# Noctua.net
KiCad netlist of a schematic drawn in EAGLE
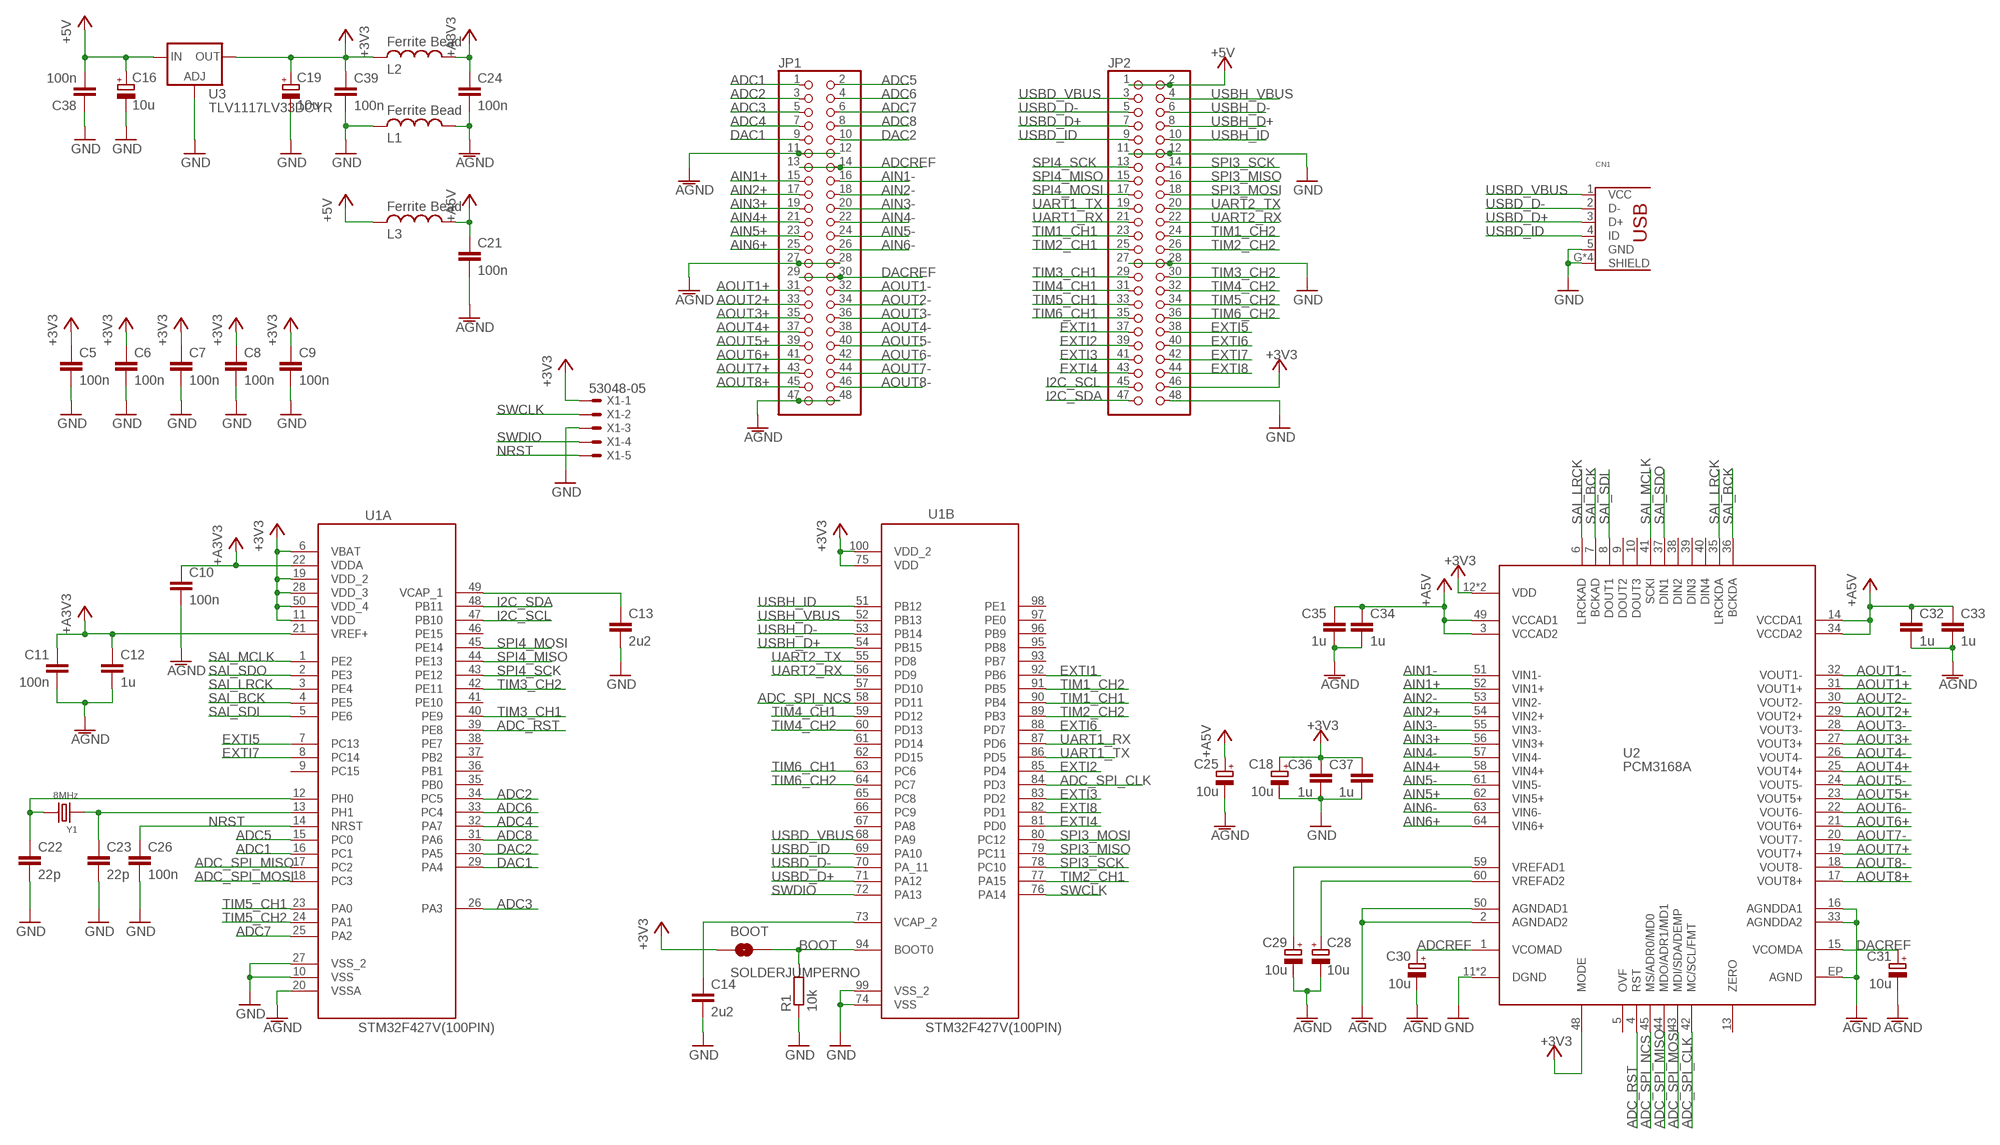
[diagram p0: schematic, sheet 1]

(export (version "E")
  (design (tool "Eeschema 10.0.6"))
  (components
    (comp (ref "BOOT")
      (value "SOLDERJUMPERNO")
      (footprint "eagle-import:SJ_2S-NO")
      (libsource (lib "eagle-import") (part "SOLDERJUMPERNO"))
    )
    (comp (ref "C5")
      (value "100n")
      (footprint "eagle-import:C0603")
      (libsource (lib "eagle-import") (part "C-EUC0603"))
    )
    (comp (ref "C6")
      (value "100n")
      (footprint "eagle-import:C0603")
      (libsource (lib "eagle-import") (part "C-EUC0603"))
    )
    (comp (ref "C7")
      (value "100n")
      (footprint "eagle-import:C0603")
      (libsource (lib "eagle-import") (part "C-EUC0603"))
    )
    (comp (ref "C8")
      (value "100n")
      (footprint "eagle-import:C0603")
      (libsource (lib "eagle-import") (part "C-EUC0603"))
    )
    (comp (ref "C9")
      (value "100n")
      (footprint "eagle-import:C0603")
      (libsource (lib "eagle-import") (part "C-EUC0603"))
    )
    (comp (ref "C10")
      (value "100n")
      (footprint "eagle-import:C0603")
      (libsource (lib "eagle-import") (part "C-EUC0603"))
    )
    (comp (ref "C11")
      (value "100n")
      (footprint "eagle-import:C0603")
      (libsource (lib "eagle-import") (part "C-EUC0603"))
    )
    (comp (ref "C12")
      (value "1u")
      (footprint "eagle-import:C0603")
      (libsource (lib "eagle-import") (part "C-EUC0603"))
    )
    (comp (ref "C13")
      (value "2u2")
      (footprint "eagle-import:C0603")
      (libsource (lib "eagle-import") (part "C-EUC0603"))
    )
    (comp (ref "C14")
      (value "2u2")
      (footprint "eagle-import:C0603")
      (libsource (lib "eagle-import") (part "C-EUC0603"))
    )
    (comp (ref "C16")
      (value "10u")
      (footprint "eagle-import:UD-4X5,8_NICHICON")
      (libsource (lib "eagle-import") (part "CPOL-EUUD-4X5,8"))
    )
    (comp (ref "C18")
      (value "10u")
      (footprint "eagle-import:UD-4X5,8_NICHICON")
      (libsource (lib "eagle-import") (part "CPOL-EUUD-4X5,8"))
    )
    (comp (ref "C19")
      (value "10u")
      (footprint "eagle-import:UD-4X5,8_NICHICON")
      (libsource (lib "eagle-import") (part "CPOL-EUUD-4X5,8"))
    )
    (comp (ref "C21")
      (value "100n")
      (footprint "eagle-import:C0603")
      (libsource (lib "eagle-import") (part "C-EUC0603"))
    )
    (comp (ref "C22")
      (value "22p")
      (footprint "eagle-import:C0603")
      (libsource (lib "eagle-import") (part "C-EUC0603"))
    )
    (comp (ref "C23")
      (value "22p")
      (footprint "eagle-import:C0603")
      (libsource (lib "eagle-import") (part "C-EUC0603"))
    )
    (comp (ref "C24")
      (value "100n")
      (footprint "eagle-import:C0603")
      (libsource (lib "eagle-import") (part "C-EUC0603"))
    )
    (comp (ref "C25")
      (value "10u")
      (footprint "eagle-import:UD-4X5,8_NICHICON")
      (libsource (lib "eagle-import") (part "CPOL-EUUD-4X5,8"))
    )
    (comp (ref "C26")
      (value "100n")
      (footprint "eagle-import:C0603")
      (libsource (lib "eagle-import") (part "C-EUC0603"))
    )
    (comp (ref "C28")
      (value "10u")
      (footprint "eagle-import:UD-4X5,8_NICHICON")
      (libsource (lib "eagle-import") (part "CPOL-EUUD-4X5,8"))
    )
    (comp (ref "C29")
      (value "10u")
      (footprint "eagle-import:UD-4X5,8_NICHICON")
      (libsource (lib "eagle-import") (part "CPOL-EUUD-4X5,8"))
    )
    (comp (ref "C30")
      (value "10u")
      (footprint "eagle-import:UD-4X5,8_NICHICON")
      (libsource (lib "eagle-import") (part "CPOL-EUUD-4X5,8"))
    )
    (comp (ref "C31")
      (value "10u")
      (footprint "eagle-import:UD-4X5,8_NICHICON")
      (libsource (lib "eagle-import") (part "CPOL-EUUD-4X5,8"))
    )
    (comp (ref "C32")
      (value "1u")
      (footprint "eagle-import:C0603")
      (libsource (lib "eagle-import") (part "C-EUC0603"))
    )
    (comp (ref "C33")
      (value "1u")
      (footprint "eagle-import:C0603")
      (libsource (lib "eagle-import") (part "C-EUC0603"))
    )
    (comp (ref "C34")
      (value "1u")
      (footprint "eagle-import:C0603")
      (libsource (lib "eagle-import") (part "C-EUC0603"))
    )
    (comp (ref "C35")
      (value "1u")
      (footprint "eagle-import:C0603")
      (libsource (lib "eagle-import") (part "C-EUC0603"))
    )
    (comp (ref "C36")
      (value "1u")
      (footprint "eagle-import:C0603")
      (libsource (lib "eagle-import") (part "C-EUC0603"))
    )
    (comp (ref "C37")
      (value "1u")
      (footprint "eagle-import:C0603")
      (libsource (lib "eagle-import") (part "C-EUC0603"))
    )
    (comp (ref "C38")
      (value "100n")
      (footprint "eagle-import:C0603")
      (libsource (lib "eagle-import") (part "C-EUC0603"))
    )
    (comp (ref "C39")
      (value "100n")
      (footprint "eagle-import:C0603")
      (libsource (lib "eagle-import") (part "C-EUC0603"))
    )
    (comp (ref "CN1")
      (value "USB_HRS_ZX62-B-5PA(11)MICRO.B")
      (footprint "eagle-import:HRS_ZX62RD-AB-5P8")
      (libsource (lib "eagle-import") (part "USB_HRS_ZX62-B-5PA(11)MICRO.B"))
    )
    (comp (ref "JP1")
      (value "PINHD-2X24")
      (footprint "eagle-import:2X24")
      (libsource (lib "eagle-import") (part "PINHD-2X24"))
    )
    (comp (ref "JP2")
      (value "PINHD-2X24")
      (footprint "eagle-import:2X24")
      (libsource (lib "eagle-import") (part "PINHD-2X24"))
    )
    (comp (ref "L1")
      (value "Ferrite Bead")
      (footprint "eagle-import:0603")
      (libsource (lib "eagle-import") (part "INDUCTOR"))
    )
    (comp (ref "L2")
      (value "Ferrite Bead")
      (footprint "eagle-import:0603")
      (libsource (lib "eagle-import") (part "INDUCTOR"))
    )
    (comp (ref "L3")
      (value "Ferrite Bead")
      (footprint "eagle-import:0603")
      (libsource (lib "eagle-import") (part "INDUCTOR"))
    )
    (comp (ref "R1")
      (value "10k")
      (footprint "eagle-import:0603@1")
      (libsource (lib "eagle-import") (part "R-EU_0603"))
    )
    (comp (ref "U1")
      (value "STM32F427V(100PIN)")
      (footprint "eagle-import:QFP50P1600X1600X160-100N")
      (libsource (lib "eagle-import") (part "STM32F42XV/43XV(100PIN)"))
    )
    (comp (ref "U2")
      (value "PCM3168A")
      (footprint "eagle-import:PQFP64")
      (libsource (lib "eagle-import") (part "PCM3168A"))
    )
    (comp (ref "U3")
      (value "TLV1117LV33DCYR")
      (footprint "eagle-import:SOT223")
      (libsource (lib "eagle-import") (part "LD117A?S33TR"))
    )
    (comp (ref "X1")
      (value "53048-05")
      (footprint "eagle-import:53048-05")
      (fields (field (name "MF") "MOLEX") (field (name "MPN") "53048-0510"))
      (libsource (lib "eagle-import") (part "53?-05048"))
    )
    (comp (ref "Y1")
      (value "8MHz")
      (footprint "eagle-import:X2-SMD-5.0X3.2X1.3MM")
      (fields (field (name "MPN") "5032/2P"))
      (libsource (lib "eagle-import") (part "SMD-CRYSTAL-8MHZ-20PF-20PPM(2P-5.0X3.2MM)"))
    )
  )
  (nets
    (net (code "1") (name "+3V3") (class "Default")
      (node (ref "BOOT") (pin "1") (pinfunction "1_1") (pintype "passive"))
      (node (ref "C18") (pin "+") (pinfunction "+_+") (pintype "passive"))
      (node (ref "C19") (pin "+") (pinfunction "+_+") (pintype "passive"))
      (node (ref "C36") (pin "1") (pinfunction "1_1") (pintype "passive"))
      (node (ref "C37") (pin "1") (pinfunction "1_1") (pintype "passive"))
      (node (ref "C39") (pin "1") (pinfunction "1_1") (pintype "passive"))
      (node (ref "C5") (pin "1") (pinfunction "1_1") (pintype "passive"))
      (node (ref "C6") (pin "1") (pinfunction "1_1") (pintype "passive"))
      (node (ref "C7") (pin "1") (pinfunction "1_1") (pintype "passive"))
      (node (ref "C8") (pin "1") (pinfunction "1_1") (pintype "passive"))
      (node (ref "C9") (pin "1") (pinfunction "1_1") (pintype "passive"))
      (node (ref "JP2") (pin "46") (pinfunction "46_46") (pintype "passive"))
      (node (ref "L2") (pin "2") (pinfunction "2_2") (pintype "passive"))
      (node (ref "U1") (pin "100") (pinfunction "VDD_2_100") (pintype "bidirectional"))
      (node (ref "U1") (pin "11") (pinfunction "VDD_11") (pintype "bidirectional"))
      (node (ref "U1") (pin "19") (pinfunction "VDD_2_19") (pintype "bidirectional"))
      (node (ref "U1") (pin "28") (pinfunction "VDD_3_28") (pintype "bidirectional"))
      (node (ref "U1") (pin "50") (pinfunction "VDD_4_50") (pintype "bidirectional"))
      (node (ref "U1") (pin "6") (pinfunction "VBAT_6") (pintype "bidirectional"))
      (node (ref "U1") (pin "75") (pinfunction "VDD_75") (pintype "bidirectional"))
      (node (ref "U2") (pin "12") (pinfunction "VDD_12") (pintype "bidirectional"))
      (node (ref "U2") (pin "46") (pinfunction "VDD_46") (pintype "bidirectional"))
      (node (ref "U2") (pin "48") (pinfunction "MODE_48") (pintype "bidirectional"))
      (node (ref "U3") (pin "4") (pinfunction "OUT_4") (pintype "passive"))
      (node (ref "X1") (pin "1") (pinfunction "S_1") (pintype "passive"))
    )
    (net (code "2") (name "+5V") (class "Default")
      (node (ref "C16") (pin "+") (pinfunction "+_+") (pintype "passive"))
      (node (ref "C38") (pin "2") (pinfunction "2_2") (pintype "passive"))
      (node (ref "JP2") (pin "1") (pinfunction "1_1") (pintype "passive"))
      (node (ref "JP2") (pin "2") (pinfunction "2_2") (pintype "passive"))
      (node (ref "L3") (pin "2") (pinfunction "2_2") (pintype "passive"))
      (node (ref "U3") (pin "3") (pinfunction "IN_3") (pintype "input"))
    )
    (net (code "3") (name "+A3V3") (class "Default")
      (node (ref "C10") (pin "1") (pinfunction "1_1") (pintype "passive"))
      (node (ref "C11") (pin "1") (pinfunction "1_1") (pintype "passive"))
      (node (ref "C12") (pin "1") (pinfunction "1_1") (pintype "passive"))
      (node (ref "C24") (pin "1") (pinfunction "1_1") (pintype "passive"))
      (node (ref "L2") (pin "1") (pinfunction "1_1") (pintype "passive"))
      (node (ref "U1") (pin "21") (pinfunction "VREF+_21") (pintype "bidirectional"))
      (node (ref "U1") (pin "22") (pinfunction "VDDA_22") (pintype "bidirectional"))
    )
    (net (code "4") (name "+A5V") (class "Default")
      (node (ref "C21") (pin "1") (pinfunction "1_1") (pintype "passive"))
      (node (ref "C25") (pin "+") (pinfunction "+_+") (pintype "passive"))
      (node (ref "C32") (pin "1") (pinfunction "1_1") (pintype "passive"))
      (node (ref "C33") (pin "1") (pinfunction "1_1") (pintype "passive"))
      (node (ref "C34") (pin "1") (pinfunction "1_1") (pintype "passive"))
      (node (ref "C35") (pin "1") (pinfunction "1_1") (pintype "passive"))
      (node (ref "L3") (pin "1") (pinfunction "1_1") (pintype "passive"))
      (node (ref "U2") (pin "14") (pinfunction "VCCDA1_14") (pintype "bidirectional"))
      (node (ref "U2") (pin "3") (pinfunction "VCCAD2_3") (pintype "bidirectional"))
      (node (ref "U2") (pin "34") (pinfunction "VCCDA2_34") (pintype "bidirectional"))
      (node (ref "U2") (pin "49") (pinfunction "VCCAD1_49") (pintype "bidirectional"))
    )
    (net (code "5") (name "/ADC1") (class "Default")
      (node (ref "JP1") (pin "1") (pinfunction "1_1") (pintype "passive"))
      (node (ref "U1") (pin "16") (pinfunction "PC1_16") (pintype "bidirectional"))
    )
    (net (code "6") (name "/ADC2") (class "Default")
      (node (ref "JP1") (pin "3") (pinfunction "3_3") (pintype "passive"))
      (node (ref "U1") (pin "34") (pinfunction "PC5_34") (pintype "bidirectional"))
    )
    (net (code "7") (name "/ADC3") (class "Default")
      (node (ref "JP1") (pin "5") (pinfunction "5_5") (pintype "passive"))
      (node (ref "U1") (pin "26") (pinfunction "PA3_26") (pintype "bidirectional"))
    )
    (net (code "8") (name "/ADC4") (class "Default")
      (node (ref "JP1") (pin "7") (pinfunction "7_7") (pintype "passive"))
      (node (ref "U1") (pin "32") (pinfunction "PA7_32") (pintype "bidirectional"))
    )
    (net (code "9") (name "/ADC5") (class "Default")
      (node (ref "JP1") (pin "2") (pinfunction "2_2") (pintype "passive"))
      (node (ref "U1") (pin "15") (pinfunction "PC0_15") (pintype "bidirectional"))
    )
    (net (code "10") (name "/ADC6") (class "Default")
      (node (ref "JP1") (pin "4") (pinfunction "4_4") (pintype "passive"))
      (node (ref "U1") (pin "33") (pinfunction "PC4_33") (pintype "bidirectional"))
    )
    (net (code "11") (name "/ADC7") (class "Default")
      (node (ref "JP1") (pin "6") (pinfunction "6_6") (pintype "passive"))
      (node (ref "U1") (pin "25") (pinfunction "PA2_25") (pintype "bidirectional"))
    )
    (net (code "12") (name "/ADC8") (class "Default")
      (node (ref "JP1") (pin "8") (pinfunction "8_8") (pintype "passive"))
      (node (ref "U1") (pin "31") (pinfunction "PA6_31") (pintype "bidirectional"))
    )
    (net (code "13") (name "/ADCREF") (class "Default")
      (node (ref "C30") (pin "+") (pinfunction "+_+") (pintype "passive"))
      (node (ref "JP1") (pin "13") (pinfunction "13_13") (pintype "passive"))
      (node (ref "JP1") (pin "14") (pinfunction "14_14") (pintype "passive"))
      (node (ref "U2") (pin "1") (pinfunction "VCOMAD_1") (pintype "bidirectional"))
    )
    (net (code "14") (name "/ADC_RST") (class "Default")
      (node (ref "U1") (pin "39") (pinfunction "PE8_39") (pintype "bidirectional"))
      (node (ref "U2") (pin "4") (pinfunction "RST_4") (pintype "bidirectional"))
    )
    (net (code "15") (name "/ADC_SPI_CLK") (class "Default")
      (node (ref "U1") (pin "84") (pinfunction "PD3_84") (pintype "bidirectional"))
      (node (ref "U2") (pin "42") (pinfunction "MC/SCL/FMT_42") (pintype "bidirectional"))
    )
    (net (code "16") (name "/ADC_SPI_MISO") (class "Default")
      (node (ref "U1") (pin "17") (pinfunction "PC2_17") (pintype "bidirectional"))
      (node (ref "U2") (pin "44") (pinfunction "MDO/ADR1/MD1_44") (pintype "bidirectional"))
    )
    (net (code "17") (name "/ADC_SPI_MOSI") (class "Default")
      (node (ref "U1") (pin "18") (pinfunction "PC3_18") (pintype "bidirectional"))
      (node (ref "U2") (pin "43") (pinfunction "MDI/SDA/DEMP_43") (pintype "bidirectional"))
    )
    (net (code "18") (name "/ADC_SPI_NCS") (class "Default")
      (node (ref "U1") (pin "58") (pinfunction "PD11_58") (pintype "bidirectional"))
      (node (ref "U2") (pin "45") (pinfunction "MS/ADR0/MD0_45") (pintype "bidirectional"))
    )
    (net (code "19") (name "/AIN1+") (class "Default")
      (node (ref "JP1") (pin "15") (pinfunction "15_15") (pintype "passive"))
      (node (ref "U2") (pin "52") (pinfunction "VIN1+_52") (pintype "bidirectional"))
    )
    (net (code "20") (name "/AIN1-") (class "Default")
      (node (ref "JP1") (pin "16") (pinfunction "16_16") (pintype "passive"))
      (node (ref "U2") (pin "51") (pinfunction "VIN1-_51") (pintype "bidirectional"))
    )
    (net (code "21") (name "/AIN2+") (class "Default")
      (node (ref "JP1") (pin "17") (pinfunction "17_17") (pintype "passive"))
      (node (ref "U2") (pin "54") (pinfunction "VIN2+_54") (pintype "bidirectional"))
    )
    (net (code "22") (name "/AIN2-") (class "Default")
      (node (ref "JP1") (pin "18") (pinfunction "18_18") (pintype "passive"))
      (node (ref "U2") (pin "53") (pinfunction "VIN2-_53") (pintype "bidirectional"))
    )
    (net (code "23") (name "/AIN3+") (class "Default")
      (node (ref "JP1") (pin "19") (pinfunction "19_19") (pintype "passive"))
      (node (ref "U2") (pin "56") (pinfunction "VIN3+_56") (pintype "bidirectional"))
    )
    (net (code "24") (name "/AIN3-") (class "Default")
      (node (ref "JP1") (pin "20") (pinfunction "20_20") (pintype "passive"))
      (node (ref "U2") (pin "55") (pinfunction "VIN3-_55") (pintype "bidirectional"))
    )
    (net (code "25") (name "/AIN4+") (class "Default")
      (node (ref "JP1") (pin "21") (pinfunction "21_21") (pintype "passive"))
      (node (ref "U2") (pin "58") (pinfunction "VIN4+_58") (pintype "bidirectional"))
    )
    (net (code "26") (name "/AIN4-") (class "Default")
      (node (ref "JP1") (pin "22") (pinfunction "22_22") (pintype "passive"))
      (node (ref "U2") (pin "57") (pinfunction "VIN4-_57") (pintype "bidirectional"))
    )
    (net (code "27") (name "/AIN5+") (class "Default")
      (node (ref "JP1") (pin "23") (pinfunction "23_23") (pintype "passive"))
      (node (ref "U2") (pin "62") (pinfunction "VIN5+_62") (pintype "bidirectional"))
    )
    (net (code "28") (name "/AIN5-") (class "Default")
      (node (ref "JP1") (pin "24") (pinfunction "24_24") (pintype "passive"))
      (node (ref "U2") (pin "61") (pinfunction "VIN5-_61") (pintype "bidirectional"))
    )
    (net (code "29") (name "/AIN6+") (class "Default")
      (node (ref "JP1") (pin "25") (pinfunction "25_25") (pintype "passive"))
      (node (ref "U2") (pin "64") (pinfunction "VIN6+_64") (pintype "bidirectional"))
    )
    (net (code "30") (name "/AIN6-") (class "Default")
      (node (ref "JP1") (pin "26") (pinfunction "26_26") (pintype "passive"))
      (node (ref "U2") (pin "63") (pinfunction "VIN6-_63") (pintype "bidirectional"))
    )
    (net (code "31") (name "/AOUT1+") (class "Default")
      (node (ref "JP1") (pin "31") (pinfunction "31_31") (pintype "passive"))
      (node (ref "U2") (pin "31") (pinfunction "VOUT1+_31") (pintype "bidirectional"))
    )
    (net (code "32") (name "/AOUT1-") (class "Default")
      (node (ref "JP1") (pin "32") (pinfunction "32_32") (pintype "passive"))
      (node (ref "U2") (pin "32") (pinfunction "VOUT1-_32") (pintype "bidirectional"))
    )
    (net (code "33") (name "/AOUT2+") (class "Default")
      (node (ref "JP1") (pin "33") (pinfunction "33_33") (pintype "passive"))
      (node (ref "U2") (pin "29") (pinfunction "VOUT2+_29") (pintype "bidirectional"))
    )
    (net (code "34") (name "/AOUT2-") (class "Default")
      (node (ref "JP1") (pin "34") (pinfunction "34_34") (pintype "passive"))
      (node (ref "U2") (pin "30") (pinfunction "VOUT2-_30") (pintype "bidirectional"))
    )
    (net (code "35") (name "/AOUT3+") (class "Default")
      (node (ref "JP1") (pin "35") (pinfunction "35_35") (pintype "passive"))
      (node (ref "U2") (pin "27") (pinfunction "VOUT3+_27") (pintype "bidirectional"))
    )
    (net (code "36") (name "/AOUT3-") (class "Default")
      (node (ref "JP1") (pin "36") (pinfunction "36_36") (pintype "passive"))
      (node (ref "U2") (pin "28") (pinfunction "VOUT3-_28") (pintype "bidirectional"))
    )
    (net (code "37") (name "/AOUT4+") (class "Default")
      (node (ref "JP1") (pin "37") (pinfunction "37_37") (pintype "passive"))
      (node (ref "U2") (pin "25") (pinfunction "VOUT4+_25") (pintype "bidirectional"))
    )
    (net (code "38") (name "/AOUT4-") (class "Default")
      (node (ref "JP1") (pin "38") (pinfunction "38_38") (pintype "passive"))
      (node (ref "U2") (pin "26") (pinfunction "VOUT4-_26") (pintype "bidirectional"))
    )
    (net (code "39") (name "/AOUT5+") (class "Default")
      (node (ref "JP1") (pin "39") (pinfunction "39_39") (pintype "passive"))
      (node (ref "U2") (pin "23") (pinfunction "VOUT5+_23") (pintype "bidirectional"))
    )
    (net (code "40") (name "/AOUT5-") (class "Default")
      (node (ref "JP1") (pin "40") (pinfunction "40_40") (pintype "passive"))
      (node (ref "U2") (pin "24") (pinfunction "VOUT5-_24") (pintype "bidirectional"))
    )
    (net (code "41") (name "/AOUT6+") (class "Default")
      (node (ref "JP1") (pin "41") (pinfunction "41_41") (pintype "passive"))
      (node (ref "U2") (pin "21") (pinfunction "VOUT6+_21") (pintype "bidirectional"))
    )
    (net (code "42") (name "/AOUT6-") (class "Default")
      (node (ref "JP1") (pin "42") (pinfunction "42_42") (pintype "passive"))
      (node (ref "U2") (pin "22") (pinfunction "VOUT6-_22") (pintype "bidirectional"))
    )
    (net (code "43") (name "/AOUT7+") (class "Default")
      (node (ref "JP1") (pin "43") (pinfunction "43_43") (pintype "passive"))
      (node (ref "U2") (pin "19") (pinfunction "VOUT7+_19") (pintype "bidirectional"))
    )
    (net (code "44") (name "/AOUT7-") (class "Default")
      (node (ref "JP1") (pin "44") (pinfunction "44_44") (pintype "passive"))
      (node (ref "U2") (pin "20") (pinfunction "VOUT7-_20") (pintype "bidirectional"))
    )
    (net (code "45") (name "/AOUT8+") (class "Default")
      (node (ref "JP1") (pin "45") (pinfunction "45_45") (pintype "passive"))
      (node (ref "U2") (pin "17") (pinfunction "VOUT8+_17") (pintype "bidirectional"))
    )
    (net (code "46") (name "/AOUT8-") (class "Default")
      (node (ref "JP1") (pin "46") (pinfunction "46_46") (pintype "passive"))
      (node (ref "U2") (pin "18") (pinfunction "VOUT8-_18") (pintype "bidirectional"))
    )
    (net (code "47") (name "/BOOT") (class "Default")
      (node (ref "BOOT") (pin "2") (pinfunction "2_2") (pintype "passive"))
      (node (ref "R1") (pin "2") (pinfunction "2_2") (pintype "passive"))
      (node (ref "U1") (pin "94") (pinfunction "BOOT0_94") (pintype "bidirectional"))
    )
    (net (code "48") (name "/DAC1") (class "Default")
      (node (ref "JP1") (pin "9") (pinfunction "9_9") (pintype "passive"))
      (node (ref "U1") (pin "29") (pinfunction "PA4_29") (pintype "bidirectional"))
    )
    (net (code "49") (name "/DAC2") (class "Default")
      (node (ref "JP1") (pin "10") (pinfunction "10_10") (pintype "passive"))
      (node (ref "U1") (pin "30") (pinfunction "PA5_30") (pintype "bidirectional"))
    )
    (net (code "50") (name "/DACREF") (class "Default")
      (node (ref "C31") (pin "+") (pinfunction "+_+") (pintype "passive"))
      (node (ref "JP1") (pin "29") (pinfunction "29_29") (pintype "passive"))
      (node (ref "JP1") (pin "30") (pinfunction "30_30") (pintype "passive"))
      (node (ref "U2") (pin "15") (pinfunction "VCOMDA_15") (pintype "bidirectional"))
    )
    (net (code "51") (name "/EXTI1") (class "Default")
      (node (ref "JP2") (pin "37") (pinfunction "37_37") (pintype "passive"))
      (node (ref "U1") (pin "92") (pinfunction "PB6_92") (pintype "bidirectional"))
    )
    (net (code "52") (name "/EXTI2") (class "Default")
      (node (ref "JP2") (pin "39") (pinfunction "39_39") (pintype "passive"))
      (node (ref "U1") (pin "85") (pinfunction "PD4_85") (pintype "bidirectional"))
    )
    (net (code "53") (name "/EXTI3") (class "Default")
      (node (ref "JP2") (pin "41") (pinfunction "41_41") (pintype "passive"))
      (node (ref "U1") (pin "83") (pinfunction "PD2_83") (pintype "bidirectional"))
    )
    (net (code "54") (name "/EXTI4") (class "Default")
      (node (ref "JP2") (pin "43") (pinfunction "43_43") (pintype "passive"))
      (node (ref "U1") (pin "81") (pinfunction "PD0_81") (pintype "bidirectional"))
    )
    (net (code "55") (name "/EXTI5") (class "Default")
      (node (ref "JP2") (pin "38") (pinfunction "38_38") (pintype "passive"))
      (node (ref "U1") (pin "7") (pinfunction "PC13_7") (pintype "bidirectional"))
    )
    (net (code "56") (name "/EXTI6") (class "Default")
      (node (ref "JP2") (pin "40") (pinfunction "40_40") (pintype "passive"))
      (node (ref "U1") (pin "88") (pinfunction "PD7_88") (pintype "bidirectional"))
    )
    (net (code "57") (name "/EXTI7") (class "Default")
      (node (ref "JP2") (pin "42") (pinfunction "42_42") (pintype "passive"))
      (node (ref "U1") (pin "8") (pinfunction "PC14_8") (pintype "bidirectional"))
    )
    (net (code "58") (name "/EXTI8") (class "Default")
      (node (ref "JP2") (pin "44") (pinfunction "44_44") (pintype "passive"))
      (node (ref "U1") (pin "82") (pinfunction "PD1_82") (pintype "bidirectional"))
    )
    (net (code "59") (name "/I2C_SCL") (class "Default")
      (node (ref "JP2") (pin "45") (pinfunction "45_45") (pintype "passive"))
      (node (ref "U1") (pin "47") (pinfunction "PB10_47") (pintype "bidirectional"))
    )
    (net (code "60") (name "/I2C_SDA") (class "Default")
      (node (ref "JP2") (pin "47") (pinfunction "47_47") (pintype "passive"))
      (node (ref "U1") (pin "48") (pinfunction "PB11_48") (pintype "bidirectional"))
    )
    (net (code "61") (name "/NRST") (class "Default")
      (node (ref "C26") (pin "1") (pinfunction "1_1") (pintype "passive"))
      (node (ref "U1") (pin "14") (pinfunction "NRST_14") (pintype "bidirectional"))
      (node (ref "X1") (pin "5") (pinfunction "S_5") (pintype "passive"))
    )
    (net (code "62") (name "/SAI_BCK") (class "Default")
      (node (ref "U1") (pin "4") (pinfunction "PE5_4") (pintype "bidirectional"))
      (node (ref "U2") (pin "36") (pinfunction "BCKDA_36") (pintype "bidirectional"))
      (node (ref "U2") (pin "7") (pinfunction "BCKAD_7") (pintype "bidirectional"))
    )
    (net (code "63") (name "/SAI_LRCK") (class "Default")
      (node (ref "U1") (pin "3") (pinfunction "PE4_3") (pintype "bidirectional"))
      (node (ref "U2") (pin "35") (pinfunction "LRCKDA_35") (pintype "bidirectional"))
      (node (ref "U2") (pin "6") (pinfunction "LRCKAD_6") (pintype "bidirectional"))
    )
    (net (code "64") (name "/SAI_MCLK") (class "Default")
      (node (ref "U1") (pin "1") (pinfunction "PE2_1") (pintype "bidirectional"))
      (node (ref "U2") (pin "41") (pinfunction "SCKI_41") (pintype "bidirectional"))
    )
    (net (code "65") (name "/SAI_SDI") (class "Default")
      (node (ref "U1") (pin "5") (pinfunction "PE6_5") (pintype "bidirectional"))
      (node (ref "U2") (pin "8") (pinfunction "DOUT1_8") (pintype "bidirectional"))
    )
    (net (code "66") (name "/SAI_SDO") (class "Default")
      (node (ref "U1") (pin "2") (pinfunction "PE3_2") (pintype "bidirectional"))
      (node (ref "U2") (pin "37") (pinfunction "DIN1_37") (pintype "bidirectional"))
    )
    (net (code "67") (name "/SPI3_MISO") (class "Default")
      (node (ref "JP2") (pin "16") (pinfunction "16_16") (pintype "passive"))
      (node (ref "U1") (pin "79") (pinfunction "PC11_79") (pintype "bidirectional"))
    )
    (net (code "68") (name "/SPI3_MOSI") (class "Default")
      (node (ref "JP2") (pin "18") (pinfunction "18_18") (pintype "passive"))
      (node (ref "U1") (pin "80") (pinfunction "PC12_80") (pintype "bidirectional"))
    )
    (net (code "69") (name "/SPI3_SCK") (class "Default")
      (node (ref "JP2") (pin "14") (pinfunction "14_14") (pintype "passive"))
      (node (ref "U1") (pin "78") (pinfunction "PC10_78") (pintype "bidirectional"))
    )
    (net (code "70") (name "/SPI4_MISO") (class "Default")
      (node (ref "JP2") (pin "15") (pinfunction "15_15") (pintype "passive"))
      (node (ref "U1") (pin "44") (pinfunction "PE13_44") (pintype "bidirectional"))
    )
    (net (code "71") (name "/SPI4_MOSI") (class "Default")
      (node (ref "JP2") (pin "17") (pinfunction "17_17") (pintype "passive"))
      (node (ref "U1") (pin "45") (pinfunction "PE14_45") (pintype "bidirectional"))
    )
    (net (code "72") (name "/SPI4_SCK") (class "Default")
      (node (ref "JP2") (pin "13") (pinfunction "13_13") (pintype "passive"))
      (node (ref "U1") (pin "43") (pinfunction "PE12_43") (pintype "bidirectional"))
    )
    (net (code "73") (name "/SWCLK") (class "Default")
      (node (ref "U1") (pin "76") (pinfunction "PA14_76") (pintype "bidirectional"))
      (node (ref "X1") (pin "2") (pinfunction "S_2") (pintype "passive"))
    )
    (net (code "74") (name "/SWDIO") (class "Default")
      (node (ref "U1") (pin "72") (pinfunction "PA13_72") (pintype "bidirectional"))
      (node (ref "X1") (pin "4") (pinfunction "S_4") (pintype "passive"))
    )
    (net (code "75") (name "/TIM1_CH1") (class "Default")
      (node (ref "JP2") (pin "23") (pinfunction "23_23") (pintype "passive"))
      (node (ref "U1") (pin "90") (pinfunction "PB4_90") (pintype "bidirectional"))
    )
    (net (code "76") (name "/TIM1_CH2") (class "Default")
      (node (ref "JP2") (pin "24") (pinfunction "24_24") (pintype "passive"))
      (node (ref "U1") (pin "91") (pinfunction "PB5_91") (pintype "bidirectional"))
    )
    (net (code "77") (name "/TIM2_CH1") (class "Default")
      (node (ref "JP2") (pin "25") (pinfunction "25_25") (pintype "passive"))
      (node (ref "U1") (pin "77") (pinfunction "PA15_77") (pintype "bidirectional"))
    )
    (net (code "78") (name "/TIM2_CH2") (class "Default")
      (node (ref "JP2") (pin "26") (pinfunction "26_26") (pintype "passive"))
      (node (ref "U1") (pin "89") (pinfunction "PB3_89") (pintype "bidirectional"))
    )
    (net (code "79") (name "/TIM3_CH1") (class "Default")
      (node (ref "JP2") (pin "29") (pinfunction "29_29") (pintype "passive"))
      (node (ref "U1") (pin "40") (pinfunction "PE9_40") (pintype "bidirectional"))
    )
    (net (code "80") (name "/TIM3_CH2") (class "Default")
      (node (ref "JP2") (pin "30") (pinfunction "30_30") (pintype "passive"))
      (node (ref "U1") (pin "42") (pinfunction "PE11_42") (pintype "bidirectional"))
    )
    (net (code "81") (name "/TIM4_CH1") (class "Default")
      (node (ref "JP2") (pin "31") (pinfunction "31_31") (pintype "passive"))
      (node (ref "U1") (pin "59") (pinfunction "PD12_59") (pintype "bidirectional"))
    )
    (net (code "82") (name "/TIM4_CH2") (class "Default")
      (node (ref "JP2") (pin "32") (pinfunction "32_32") (pintype "passive"))
      (node (ref "U1") (pin "60") (pinfunction "PD13_60") (pintype "bidirectional"))
    )
    (net (code "83") (name "/TIM5_CH1") (class "Default")
      (node (ref "JP2") (pin "33") (pinfunction "33_33") (pintype "passive"))
      (node (ref "U1") (pin "23") (pinfunction "PA0_23") (pintype "bidirectional"))
    )
    (net (code "84") (name "/TIM5_CH2") (class "Default")
      (node (ref "JP2") (pin "34") (pinfunction "34_34") (pintype "passive"))
      (node (ref "U1") (pin "24") (pinfunction "PA1_24") (pintype "bidirectional"))
    )
    (net (code "85") (name "/TIM6_CH1") (class "Default")
      (node (ref "JP2") (pin "35") (pinfunction "35_35") (pintype "passive"))
      (node (ref "U1") (pin "63") (pinfunction "PC6_63") (pintype "bidirectional"))
    )
    (net (code "86") (name "/TIM6_CH2") (class "Default")
      (node (ref "JP2") (pin "36") (pinfunction "36_36") (pintype "passive"))
      (node (ref "U1") (pin "64") (pinfunction "PC7_64") (pintype "bidirectional"))
    )
    (net (code "87") (name "/UART1_RX") (class "Default")
      (node (ref "JP2") (pin "21") (pinfunction "21_21") (pintype "passive"))
      (node (ref "U1") (pin "87") (pinfunction "PD6_87") (pintype "bidirectional"))
    )
    (net (code "88") (name "/UART1_TX") (class "Default")
      (node (ref "JP2") (pin "19") (pinfunction "19_19") (pintype "passive"))
      (node (ref "U1") (pin "86") (pinfunction "PD5_86") (pintype "bidirectional"))
    )
    (net (code "89") (name "/UART2_RX") (class "Default")
      (node (ref "JP2") (pin "22") (pinfunction "22_22") (pintype "passive"))
      (node (ref "U1") (pin "56") (pinfunction "PD9_56") (pintype "bidirectional"))
    )
    (net (code "90") (name "/UART2_TX") (class "Default")
      (node (ref "JP2") (pin "20") (pinfunction "20_20") (pintype "passive"))
      (node (ref "U1") (pin "55") (pinfunction "PD8_55") (pintype "bidirectional"))
    )
    (net (code "91") (name "/USBD_D+") (class "Default")
      (node (ref "CN1") (pin "3") (pinfunction "D+_3") (pintype "bidirectional"))
      (node (ref "JP2") (pin "7") (pinfunction "7_7") (pintype "passive"))
      (node (ref "U1") (pin "71") (pinfunction "PA12_71") (pintype "bidirectional"))
    )
    (net (code "92") (name "/USBD_D-") (class "Default")
      (node (ref "CN1") (pin "2") (pinfunction "D-_2") (pintype "bidirectional"))
      (node (ref "JP2") (pin "5") (pinfunction "5_5") (pintype "passive"))
      (node (ref "U1") (pin "70") (pinfunction "PA_11_70") (pintype "bidirectional"))
    )
    (net (code "93") (name "/USBD_ID") (class "Default")
      (node (ref "CN1") (pin "4") (pinfunction "ID_4") (pintype "bidirectional"))
      (node (ref "JP2") (pin "9") (pinfunction "9_9") (pintype "passive"))
      (node (ref "U1") (pin "69") (pinfunction "PA10_69") (pintype "bidirectional"))
    )
    (net (code "94") (name "/USBD_VBUS") (class "Default")
      (node (ref "CN1") (pin "1") (pinfunction "VCC_1") (pintype "bidirectional"))
      (node (ref "JP2") (pin "3") (pinfunction "3_3") (pintype "passive"))
      (node (ref "U1") (pin "68") (pinfunction "PA9_68") (pintype "bidirectional"))
    )
    (net (code "95") (name "/USBH_D+") (class "Default")
      (node (ref "JP2") (pin "8") (pinfunction "8_8") (pintype "passive"))
      (node (ref "U1") (pin "54") (pinfunction "PB15_54") (pintype "bidirectional"))
    )
    (net (code "96") (name "/USBH_D-") (class "Default")
      (node (ref "JP2") (pin "6") (pinfunction "6_6") (pintype "passive"))
      (node (ref "U1") (pin "53") (pinfunction "PB14_53") (pintype "bidirectional"))
    )
    (net (code "97") (name "/USBH_ID") (class "Default")
      (node (ref "JP2") (pin "10") (pinfunction "10_10") (pintype "passive"))
      (node (ref "U1") (pin "51") (pinfunction "PB12_51") (pintype "bidirectional"))
    )
    (net (code "98") (name "/USBH_VBUS") (class "Default")
      (node (ref "JP2") (pin "4") (pinfunction "4_4") (pintype "passive"))
      (node (ref "U1") (pin "52") (pinfunction "PB13_52") (pintype "bidirectional"))
    )
    (net (code "99") (name "AGND") (class "Default")
      (node (ref "C10") (pin "2") (pinfunction "2_2") (pintype "passive"))
      (node (ref "C11") (pin "2") (pinfunction "2_2") (pintype "passive"))
      (node (ref "C12") (pin "2") (pinfunction "2_2") (pintype "passive"))
      (node (ref "C21") (pin "2") (pinfunction "2_2") (pintype "passive"))
      (node (ref "C24") (pin "2") (pinfunction "2_2") (pintype "passive"))
      (node (ref "C25") (pin "-") (pinfunction "-_-") (pintype "passive"))
      (node (ref "C28") (pin "-") (pinfunction "-_-") (pintype "passive"))
      (node (ref "C29") (pin "-") (pinfunction "-_-") (pintype "passive"))
      (node (ref "C30") (pin "-") (pinfunction "-_-") (pintype "passive"))
      (node (ref "C31") (pin "-") (pinfunction "-_-") (pintype "passive"))
      (node (ref "C32") (pin "2") (pinfunction "2_2") (pintype "passive"))
      (node (ref "C33") (pin "2") (pinfunction "2_2") (pintype "passive"))
      (node (ref "C34") (pin "2") (pinfunction "2_2") (pintype "passive"))
      (node (ref "C35") (pin "2") (pinfunction "2_2") (pintype "passive"))
      (node (ref "JP1") (pin "11") (pinfunction "11_11") (pintype "passive"))
      (node (ref "JP1") (pin "12") (pinfunction "12_12") (pintype "passive"))
      (node (ref "JP1") (pin "27") (pinfunction "27_27") (pintype "passive"))
      (node (ref "JP1") (pin "28") (pinfunction "28_28") (pintype "passive"))
      (node (ref "JP1") (pin "47") (pinfunction "47_47") (pintype "passive"))
      (node (ref "JP1") (pin "48") (pinfunction "48_48") (pintype "passive"))
      (node (ref "L1") (pin "1") (pinfunction "1_1") (pintype "passive"))
      (node (ref "U1") (pin "20") (pinfunction "VSSA_20") (pintype "bidirectional"))
      (node (ref "U2") (pin "16") (pinfunction "AGNDDA1_16") (pintype "bidirectional"))
      (node (ref "U2") (pin "2") (pinfunction "AGNDAD2_2") (pintype "bidirectional"))
      (node (ref "U2") (pin "33") (pinfunction "AGNDDA2_33") (pintype "bidirectional"))
      (node (ref "U2") (pin "50") (pinfunction "AGNDAD1_50") (pintype "bidirectional"))
      (node (ref "U2") (pin "EP") (pinfunction "AGND_EP") (pintype "bidirectional"))
    )
    (net (code "100") (name "GND") (class "Default")
      (node (ref "C13") (pin "2") (pinfunction "2_2") (pintype "passive"))
      (node (ref "C14") (pin "2") (pinfunction "2_2") (pintype "passive"))
      (node (ref "C16") (pin "-") (pinfunction "-_-") (pintype "passive"))
      (node (ref "C18") (pin "-") (pinfunction "-_-") (pintype "passive"))
      (node (ref "C19") (pin "-") (pinfunction "-_-") (pintype "passive"))
      (node (ref "C22") (pin "2") (pinfunction "2_2") (pintype "passive"))
      (node (ref "C23") (pin "2") (pinfunction "2_2") (pintype "passive"))
      (node (ref "C26") (pin "2") (pinfunction "2_2") (pintype "passive"))
      (node (ref "C36") (pin "2") (pinfunction "2_2") (pintype "passive"))
      (node (ref "C37") (pin "2") (pinfunction "2_2") (pintype "passive"))
      (node (ref "C38") (pin "1") (pinfunction "1_1") (pintype "passive"))
      (node (ref "C39") (pin "2") (pinfunction "2_2") (pintype "passive"))
      (node (ref "C5") (pin "2") (pinfunction "2_2") (pintype "passive"))
      (node (ref "C6") (pin "2") (pinfunction "2_2") (pintype "passive"))
      (node (ref "C7") (pin "2") (pinfunction "2_2") (pintype "passive"))
      (node (ref "C8") (pin "2") (pinfunction "2_2") (pintype "passive"))
      (node (ref "C9") (pin "2") (pinfunction "2_2") (pintype "passive"))
      (node (ref "CN1") (pin "5") (pinfunction "GND_5") (pintype "bidirectional"))
      (node (ref "CN1") (pin "G") (pinfunction "SHIELD_G") (pintype "bidirectional"))
      (node (ref "CN1") (pin "G2") (pinfunction "SHIELD_G2") (pintype "bidirectional"))
      (node (ref "CN1") (pin "G3") (pinfunction "SHIELD_G3") (pintype "bidirectional"))
      (node (ref "CN1") (pin "G4") (pinfunction "SHIELD_G4") (pintype "bidirectional"))
      (node (ref "JP2") (pin "11") (pinfunction "11_11") (pintype "passive"))
      (node (ref "JP2") (pin "12") (pinfunction "12_12") (pintype "passive"))
      (node (ref "JP2") (pin "27") (pinfunction "27_27") (pintype "passive"))
      (node (ref "JP2") (pin "28") (pinfunction "28_28") (pintype "passive"))
      (node (ref "JP2") (pin "48") (pinfunction "48_48") (pintype "passive"))
      (node (ref "L1") (pin "2") (pinfunction "2_2") (pintype "passive"))
      (node (ref "R1") (pin "1") (pinfunction "1_1") (pintype "passive"))
      (node (ref "U1") (pin "10") (pinfunction "VSS_10") (pintype "bidirectional"))
      (node (ref "U1") (pin "27") (pinfunction "VSS_2_27") (pintype "bidirectional"))
      (node (ref "U1") (pin "74") (pinfunction "VSS_74") (pintype "bidirectional"))
      (node (ref "U1") (pin "99") (pinfunction "VSS_2_99") (pintype "bidirectional"))
      (node (ref "U2") (pin "11") (pinfunction "DGND_11") (pintype "bidirectional"))
      (node (ref "U2") (pin "47") (pinfunction "DGND_47") (pintype "bidirectional"))
      (node (ref "U3") (pin "1") (pinfunction "ADJ_1") (pintype "input"))
      (node (ref "X1") (pin "3") (pinfunction "S_3") (pintype "passive"))
    )
    (net (code "101") (name "Net-(U1A-PH0)") (class "Default")
      (node (ref "C22") (pin "1") (pinfunction "1_1") (pintype "passive"))
      (node (ref "U1") (pin "12") (pinfunction "PH0_12") (pintype "bidirectional"))
      (node (ref "Y1") (pin "2") (pinfunction "2_2") (pintype "passive"))
    )
    (net (code "102") (name "Net-(U1A-PH1)") (class "Default")
      (node (ref "C23") (pin "1") (pinfunction "1_1") (pintype "passive"))
      (node (ref "U1") (pin "13") (pinfunction "PH1_13") (pintype "bidirectional"))
      (node (ref "Y1") (pin "1") (pinfunction "1_1") (pintype "passive"))
    )
    (net (code "103") (name "Net-(U1A-VCAP_1)") (class "Default")
      (node (ref "C13") (pin "1") (pinfunction "1_1") (pintype "passive"))
      (node (ref "U1") (pin "49") (pinfunction "VCAP_1_49") (pintype "bidirectional"))
    )
    (net (code "104") (name "Net-(U1B-VCAP_2)") (class "Default")
      (node (ref "C14") (pin "1") (pinfunction "1_1") (pintype "passive"))
      (node (ref "U1") (pin "73") (pinfunction "VCAP_2_73") (pintype "bidirectional"))
    )
    (net (code "105") (name "Net-(U2-VREFAD1)") (class "Default")
      (node (ref "C29") (pin "+") (pinfunction "+_+") (pintype "passive"))
      (node (ref "U2") (pin "59") (pinfunction "VREFAD1_59") (pintype "bidirectional"))
    )
    (net (code "106") (name "Net-(U2-VREFAD2)") (class "Default")
      (node (ref "C28") (pin "+") (pinfunction "+_+") (pintype "passive"))
      (node (ref "U2") (pin "60") (pinfunction "VREFAD2_60") (pintype "bidirectional"))
    )
    (net (code "107") (name "unconnected-(U1A-PB0-Pad35)") (class "Default")
      (node (ref "U1") (pin "35") (pinfunction "PB0_35") (pintype "bidirectional"))
    )
    (net (code "108") (name "unconnected-(U1A-PB1-Pad36)") (class "Default")
      (node (ref "U1") (pin "36") (pinfunction "PB1_36") (pintype "bidirectional"))
    )
    (net (code "109") (name "unconnected-(U1A-PB2-Pad37)") (class "Default")
      (node (ref "U1") (pin "37") (pinfunction "PB2_37") (pintype "bidirectional"))
    )
    (net (code "110") (name "unconnected-(U1A-PC15-Pad9)") (class "Default")
      (node (ref "U1") (pin "9") (pinfunction "PC15_9") (pintype "bidirectional"))
    )
    (net (code "111") (name "unconnected-(U1A-PE7-Pad38)") (class "Default")
      (node (ref "U1") (pin "38") (pinfunction "PE7_38") (pintype "bidirectional"))
    )
    (net (code "112") (name "unconnected-(U1A-PE10-Pad41)") (class "Default")
      (node (ref "U1") (pin "41") (pinfunction "PE10_41") (pintype "bidirectional"))
    )
    (net (code "113") (name "unconnected-(U1A-PE15-Pad46)") (class "Default")
      (node (ref "U1") (pin "46") (pinfunction "PE15_46") (pintype "bidirectional"))
    )
    (net (code "114") (name "unconnected-(U1B-PA8-Pad67)") (class "Default")
      (node (ref "U1") (pin "67") (pinfunction "PA8_67") (pintype "bidirectional"))
    )
    (net (code "115") (name "unconnected-(U1B-PB7-Pad93)") (class "Default")
      (node (ref "U1") (pin "93") (pinfunction "PB7_93") (pintype "bidirectional"))
    )
    (net (code "116") (name "unconnected-(U1B-PB8-Pad95)") (class "Default")
      (node (ref "U1") (pin "95") (pinfunction "PB8_95") (pintype "bidirectional"))
    )
    (net (code "117") (name "unconnected-(U1B-PB9-Pad96)") (class "Default")
      (node (ref "U1") (pin "96") (pinfunction "PB9_96") (pintype "bidirectional"))
    )
    (net (code "118") (name "unconnected-(U1B-PC8-Pad65)") (class "Default")
      (node (ref "U1") (pin "65") (pinfunction "PC8_65") (pintype "bidirectional"))
    )
    (net (code "119") (name "unconnected-(U1B-PC9-Pad66)") (class "Default")
      (node (ref "U1") (pin "66") (pinfunction "PC9_66") (pintype "bidirectional"))
    )
    (net (code "120") (name "unconnected-(U1B-PD10-Pad57)") (class "Default")
      (node (ref "U1") (pin "57") (pinfunction "PD10_57") (pintype "bidirectional"))
    )
    (net (code "121") (name "unconnected-(U1B-PD14-Pad61)") (class "Default")
      (node (ref "U1") (pin "61") (pinfunction "PD14_61") (pintype "bidirectional"))
    )
    (net (code "122") (name "unconnected-(U1B-PD15-Pad62)") (class "Default")
      (node (ref "U1") (pin "62") (pinfunction "PD15_62") (pintype "bidirectional"))
    )
    (net (code "123") (name "unconnected-(U1B-PE0-Pad97)") (class "Default")
      (node (ref "U1") (pin "97") (pinfunction "PE0_97") (pintype "bidirectional"))
    )
    (net (code "124") (name "unconnected-(U1B-PE1-Pad98)") (class "Default")
      (node (ref "U1") (pin "98") (pinfunction "PE1_98") (pintype "bidirectional"))
    )
    (net (code "125") (name "unconnected-(U2-DIN2-Pad38)") (class "Default")
      (node (ref "U2") (pin "38") (pinfunction "DIN2_38") (pintype "bidirectional"))
    )
    (net (code "126") (name "unconnected-(U2-DIN3-Pad39)") (class "Default")
      (node (ref "U2") (pin "39") (pinfunction "DIN3_39") (pintype "bidirectional"))
    )
    (net (code "127") (name "unconnected-(U2-DIN4-Pad40)") (class "Default")
      (node (ref "U2") (pin "40") (pinfunction "DIN4_40") (pintype "bidirectional"))
    )
    (net (code "128") (name "unconnected-(U2-DOUT2-Pad9)") (class "Default")
      (node (ref "U2") (pin "9") (pinfunction "DOUT2_9") (pintype "bidirectional"))
    )
    (net (code "129") (name "unconnected-(U2-DOUT3-Pad10)") (class "Default")
      (node (ref "U2") (pin "10") (pinfunction "DOUT3_10") (pintype "bidirectional"))
    )
    (net (code "130") (name "unconnected-(U2-OVF-Pad5)") (class "Default")
      (node (ref "U2") (pin "5") (pinfunction "OVF_5") (pintype "bidirectional"))
    )
    (net (code "131") (name "unconnected-(U2-ZERO-Pad13)") (class "Default")
      (node (ref "U2") (pin "13") (pinfunction "ZERO_13") (pintype "bidirectional"))
    )
  )
)
